# LTC3108_Breakout.net
KiCad netlist of a schematic drawn in EAGLE
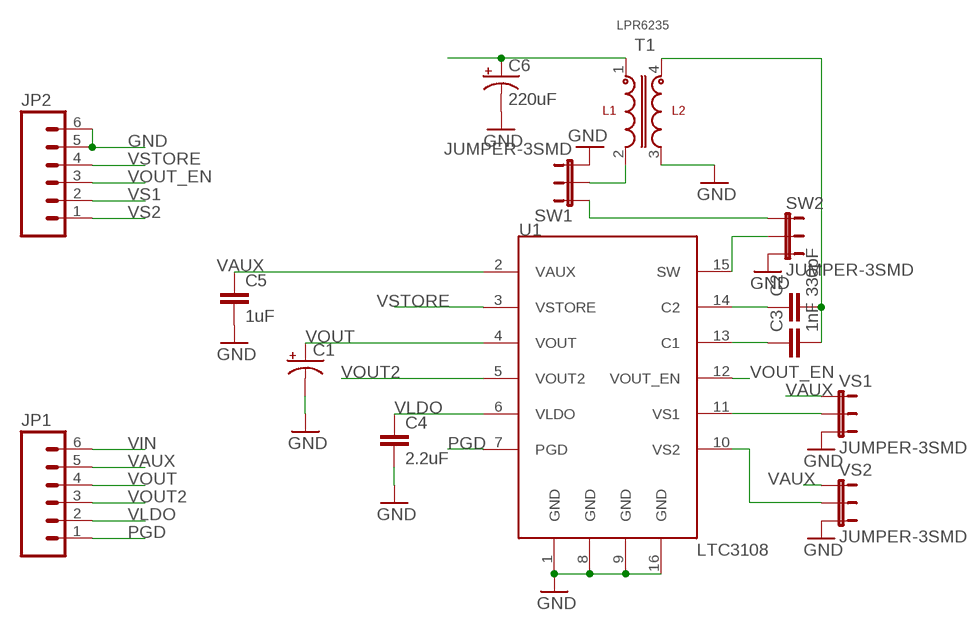
[diagram p0: schematic, sheet 1]

(export (version "E")
  (design (tool "Eeschema 10.0.6"))
  (components
    (comp (ref "C1")
      (value "CAP_POL7343")
      (footprint "eagle-import:EIA7343")
      (libsource (lib "eagle-import") (part "CAP_POL7343"))
    )
    (comp (ref "C2")
      (value "330pF")
      (footprint "eagle-import:0603-CAP")
      (libsource (lib "eagle-import") (part "CAP0603-CAP"))
    )
    (comp (ref "C3")
      (value "1nF")
      (footprint "eagle-import:0603-CAP")
      (libsource (lib "eagle-import") (part "CAP0603-CAP"))
    )
    (comp (ref "C4")
      (value "2.2uF")
      (footprint "eagle-import:0603-CAP")
      (libsource (lib "eagle-import") (part "CAP0603-CAP"))
    )
    (comp (ref "C5")
      (value "1uF")
      (footprint "eagle-import:0603-CAP")
      (libsource (lib "eagle-import") (part "CAP0603-CAP"))
    )
    (comp (ref "C6")
      (value "220uF")
      (footprint "eagle-import:EIA7343")
      (libsource (lib "eagle-import") (part "CAP_POL7343"))
    )
    (comp (ref "JP1")
      (value "M06SIP")
      (footprint "eagle-import:1X06")
      (libsource (lib "eagle-import") (part "M06SIP"))
    )
    (comp (ref "JP2")
      (value "M06SIP")
      (footprint "eagle-import:1X06")
      (libsource (lib "eagle-import") (part "M06SIP"))
    )
    (comp (ref "SW1")
      (value "JUMPER-3SMD")
      (footprint "eagle-import:SJ_3")
      (libsource (lib "eagle-import") (part "JUMPER-3SMD"))
    )
    (comp (ref "SW2")
      (value "JUMPER-3SMD")
      (footprint "eagle-import:SJ_3")
      (libsource (lib "eagle-import") (part "JUMPER-3SMD"))
    )
    (comp (ref "T1")
      (value "LPR6235")
      (footprint "eagle-import:LPR6235")
      (libsource (lib "eagle-import") (part "LPR6235"))
    )
    (comp (ref "U1")
      (value "LTC3108")
      (footprint "eagle-import:SSOP")
      (libsource (lib "eagle-import") (part "LTC3108"))
    )
    (comp (ref "VS1")
      (value "JUMPER-3SMD")
      (footprint "eagle-import:SJ_3")
      (libsource (lib "eagle-import") (part "JUMPER-3SMD"))
    )
    (comp (ref "VS2")
      (value "JUMPER-3SMD")
      (footprint "eagle-import:SJ_3")
      (libsource (lib "eagle-import") (part "JUMPER-3SMD"))
    )
  )
  (nets
    (net (code "1") (name "/PGD") (class "Default")
      (node (ref "JP1") (pin "1") (pinfunction "1_1") (pintype "passive"))
      (node (ref "U1") (pin "7") (pinfunction "PGD_7") (pintype "bidirectional"))
    )
    (net (code "2") (name "/VAUX") (class "Default")
      (node (ref "C5") (pin "1") (pinfunction "1_1") (pintype "passive"))
      (node (ref "JP1") (pin "5") (pinfunction "5_5") (pintype "passive"))
      (node (ref "U1") (pin "2") (pinfunction "VAUX_2") (pintype "bidirectional"))
      (node (ref "VS1") (pin "1") (pinfunction "1_1") (pintype "passive"))
      (node (ref "VS2") (pin "1") (pinfunction "1_1") (pintype "passive"))
    )
    (net (code "3") (name "/VIN") (class "Default")
      (node (ref "C6") (pin "A") (pinfunction "+_A") (pintype "passive"))
      (node (ref "JP1") (pin "6") (pinfunction "6_6") (pintype "passive"))
      (node (ref "T1") (pin "1") (pinfunction "1_1") (pintype "bidirectional"))
    )
    (net (code "4") (name "/VLDO") (class "Default")
      (node (ref "C4") (pin "1") (pinfunction "1_1") (pintype "passive"))
      (node (ref "JP1") (pin "2") (pinfunction "2_2") (pintype "passive"))
      (node (ref "U1") (pin "6") (pinfunction "VLDO_6") (pintype "bidirectional"))
    )
    (net (code "5") (name "/VOUT") (class "Default")
      (node (ref "C1") (pin "A") (pinfunction "+_A") (pintype "passive"))
      (node (ref "JP1") (pin "4") (pinfunction "4_4") (pintype "passive"))
      (node (ref "U1") (pin "4") (pinfunction "VOUT_4") (pintype "bidirectional"))
    )
    (net (code "6") (name "/VOUT2") (class "Default")
      (node (ref "JP1") (pin "3") (pinfunction "3_3") (pintype "passive"))
      (node (ref "U1") (pin "5") (pinfunction "VOUT2_5") (pintype "bidirectional"))
    )
    (net (code "7") (name "/VOUT_EN") (class "Default")
      (node (ref "JP2") (pin "3") (pinfunction "3_3") (pintype "passive"))
      (node (ref "U1") (pin "12") (pinfunction "VOUT_EN_12") (pintype "bidirectional"))
    )
    (net (code "8") (name "/VS1") (class "Default")
      (node (ref "JP2") (pin "2") (pinfunction "2_2") (pintype "passive"))
      (node (ref "U1") (pin "11") (pinfunction "VS1_11") (pintype "bidirectional"))
      (node (ref "VS1") (pin "2") (pinfunction "2_2") (pintype "passive"))
    )
    (net (code "9") (name "/VS2") (class "Default")
      (node (ref "JP2") (pin "1") (pinfunction "1_1") (pintype "passive"))
      (node (ref "U1") (pin "10") (pinfunction "VS2_10") (pintype "bidirectional"))
      (node (ref "VS2") (pin "2") (pinfunction "2_2") (pintype "passive"))
    )
    (net (code "10") (name "/VSTORE") (class "Default")
      (node (ref "JP2") (pin "4") (pinfunction "4_4") (pintype "passive"))
      (node (ref "U1") (pin "3") (pinfunction "VSTORE_3") (pintype "bidirectional"))
    )
    (net (code "11") (name "GND") (class "Default")
      (node (ref "C1") (pin "C") (pinfunction "-_C") (pintype "passive"))
      (node (ref "C4") (pin "2") (pinfunction "2_2") (pintype "passive"))
      (node (ref "C5") (pin "2") (pinfunction "2_2") (pintype "passive"))
      (node (ref "C6") (pin "C") (pinfunction "-_C") (pintype "passive"))
      (node (ref "JP2") (pin "5") (pinfunction "5_5") (pintype "passive"))
      (node (ref "JP2") (pin "6") (pinfunction "6_6") (pintype "passive"))
      (node (ref "SW1") (pin "3") (pinfunction "3_3") (pintype "passive"))
      (node (ref "SW2") (pin "3") (pinfunction "3_3") (pintype "passive"))
      (node (ref "T1") (pin "3") (pinfunction "3_3") (pintype "bidirectional"))
      (node (ref "U1") (pin "1") (pinfunction "GND_1") (pintype "bidirectional"))
      (node (ref "U1") (pin "16") (pinfunction "GND_16") (pintype "bidirectional"))
      (node (ref "U1") (pin "8") (pinfunction "GND_8") (pintype "bidirectional"))
      (node (ref "U1") (pin "9") (pinfunction "GND_9") (pintype "bidirectional"))
      (node (ref "VS1") (pin "3") (pinfunction "3_3") (pintype "passive"))
      (node (ref "VS2") (pin "3") (pinfunction "3_3") (pintype "passive"))
    )
    (net (code "12") (name "Net-(C2-Pad2)") (class "Default")
      (node (ref "C2") (pin "2") (pinfunction "2_2") (pintype "passive"))
      (node (ref "C3") (pin "2") (pinfunction "2_2") (pintype "passive"))
      (node (ref "T1") (pin "4") (pinfunction "4_4") (pintype "bidirectional"))
    )
    (net (code "13") (name "Net-(SW1-Pad1)") (class "Default")
      (node (ref "SW1") (pin "1") (pinfunction "1_1") (pintype "passive"))
      (node (ref "SW2") (pin "1") (pinfunction "1_1") (pintype "passive"))
    )
    (net (code "14") (name "Net-(SW1-Pad2)") (class "Default")
      (node (ref "SW1") (pin "2") (pinfunction "2_2") (pintype "passive"))
      (node (ref "T1") (pin "2") (pinfunction "2_2") (pintype "bidirectional"))
    )
    (net (code "15") (name "Net-(U1-C1)") (class "Default")
      (node (ref "C3") (pin "1") (pinfunction "1_1") (pintype "passive"))
      (node (ref "U1") (pin "13") (pinfunction "C1_13") (pintype "bidirectional"))
    )
    (net (code "16") (name "Net-(U1-C2)") (class "Default")
      (node (ref "C2") (pin "1") (pinfunction "1_1") (pintype "passive"))
      (node (ref "U1") (pin "14") (pinfunction "C2_14") (pintype "bidirectional"))
    )
    (net (code "17") (name "Net-(U1-SW)") (class "Default")
      (node (ref "SW2") (pin "2") (pinfunction "2_2") (pintype "passive"))
      (node (ref "U1") (pin "15") (pinfunction "SW_15") (pintype "bidirectional"))
    )
  )
)
